# rj45-adaptor-1-2.net
KiCad netlist of a schematic drawn in EAGLE
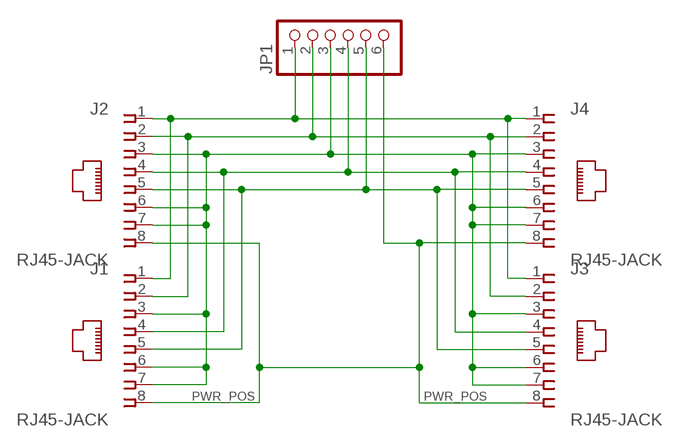
[diagram p0: schematic, sheet 1]

(export (version "E")
  (design (tool "Eeschema 10.0.6"))
  (components
    (comp (ref "J1")
      (value "RJ45-JACK")
      (footprint "eagle-import:RJ45-PULSE-E5J88")
      (libsource (lib "eagle-import") (part "RJ45-JACKRJ45-PULSE-E5J00"))
    )
    (comp (ref "J2")
      (value "RJ45-JACK")
      (footprint "eagle-import:RJ45-PULSE-E5J88")
      (libsource (lib "eagle-import") (part "RJ45-JACKRJ45-PULSE-E5J00"))
    )
    (comp (ref "J3")
      (value "RJ45-JACK")
      (footprint "eagle-import:RJ45-PULSE-E5J88")
      (libsource (lib "eagle-import") (part "RJ45-JACKRJ45-PULSE-E5J00"))
    )
    (comp (ref "J4")
      (value "RJ45-JACK")
      (footprint "eagle-import:RJ45-PULSE-E5J88")
      (libsource (lib "eagle-import") (part "RJ45-JACKRJ45-PULSE-E5J00"))
    )
    (comp (ref "JP1")
      (value "PINHD-1X6")
      (footprint "eagle-import:1X06")
      (libsource (lib "eagle-import") (part "PINHD-1X6"))
    )
  )
  (nets
    (net (code "1") (name "/PWR_POS") (class "Default")
      (node (ref "J1") (pin "8") (pinfunction "8_8") (pintype "passive"))
      (node (ref "J2") (pin "8") (pinfunction "8_8") (pintype "passive"))
      (node (ref "J3") (pin "8") (pinfunction "8_8") (pintype "passive"))
      (node (ref "J4") (pin "8") (pinfunction "8_8") (pintype "passive"))
      (node (ref "JP1") (pin "6") (pinfunction "6_6") (pintype "passive"))
    )
    (net (code "2") (name "Net-(J1-Pad1)") (class "Default")
      (node (ref "J1") (pin "1") (pinfunction "1_1") (pintype "passive"))
      (node (ref "J2") (pin "1") (pinfunction "1_1") (pintype "passive"))
      (node (ref "J3") (pin "1") (pinfunction "1_1") (pintype "passive"))
      (node (ref "J4") (pin "1") (pinfunction "1_1") (pintype "passive"))
      (node (ref "JP1") (pin "1") (pinfunction "1_1") (pintype "passive"))
    )
    (net (code "3") (name "Net-(J1-Pad2)") (class "Default")
      (node (ref "J1") (pin "2") (pinfunction "2_2") (pintype "passive"))
      (node (ref "J2") (pin "2") (pinfunction "2_2") (pintype "passive"))
      (node (ref "J3") (pin "2") (pinfunction "2_2") (pintype "passive"))
      (node (ref "J4") (pin "2") (pinfunction "2_2") (pintype "passive"))
      (node (ref "JP1") (pin "2") (pinfunction "2_2") (pintype "passive"))
    )
    (net (code "4") (name "Net-(J1-Pad3)") (class "Default")
      (node (ref "J1") (pin "3") (pinfunction "3_3") (pintype "passive"))
      (node (ref "J1") (pin "6") (pinfunction "6_6") (pintype "passive"))
      (node (ref "J1") (pin "7") (pinfunction "7_7") (pintype "passive"))
      (node (ref "J2") (pin "3") (pinfunction "3_3") (pintype "passive"))
      (node (ref "J2") (pin "6") (pinfunction "6_6") (pintype "passive"))
      (node (ref "J2") (pin "7") (pinfunction "7_7") (pintype "passive"))
      (node (ref "J3") (pin "3") (pinfunction "3_3") (pintype "passive"))
      (node (ref "J3") (pin "6") (pinfunction "6_6") (pintype "passive"))
      (node (ref "J3") (pin "7") (pinfunction "7_7") (pintype "passive"))
      (node (ref "J4") (pin "3") (pinfunction "3_3") (pintype "passive"))
      (node (ref "J4") (pin "6") (pinfunction "6_6") (pintype "passive"))
      (node (ref "J4") (pin "7") (pinfunction "7_7") (pintype "passive"))
      (node (ref "JP1") (pin "3") (pinfunction "3_3") (pintype "passive"))
    )
    (net (code "5") (name "Net-(J1-Pad4)") (class "Default")
      (node (ref "J1") (pin "4") (pinfunction "4_4") (pintype "passive"))
      (node (ref "J2") (pin "4") (pinfunction "4_4") (pintype "passive"))
      (node (ref "J3") (pin "4") (pinfunction "4_4") (pintype "passive"))
      (node (ref "J4") (pin "4") (pinfunction "4_4") (pintype "passive"))
      (node (ref "JP1") (pin "4") (pinfunction "4_4") (pintype "passive"))
    )
    (net (code "6") (name "Net-(J1-Pad5)") (class "Default")
      (node (ref "J1") (pin "5") (pinfunction "5_5") (pintype "passive"))
      (node (ref "J2") (pin "5") (pinfunction "5_5") (pintype "passive"))
      (node (ref "J3") (pin "5") (pinfunction "5_5") (pintype "passive"))
      (node (ref "J4") (pin "5") (pinfunction "5_5") (pintype "passive"))
      (node (ref "JP1") (pin "5") (pinfunction "5_5") (pintype "passive"))
    )
  )
)
